# Main_Power.net
KiCad netlist of a schematic drawn in Altium Designer
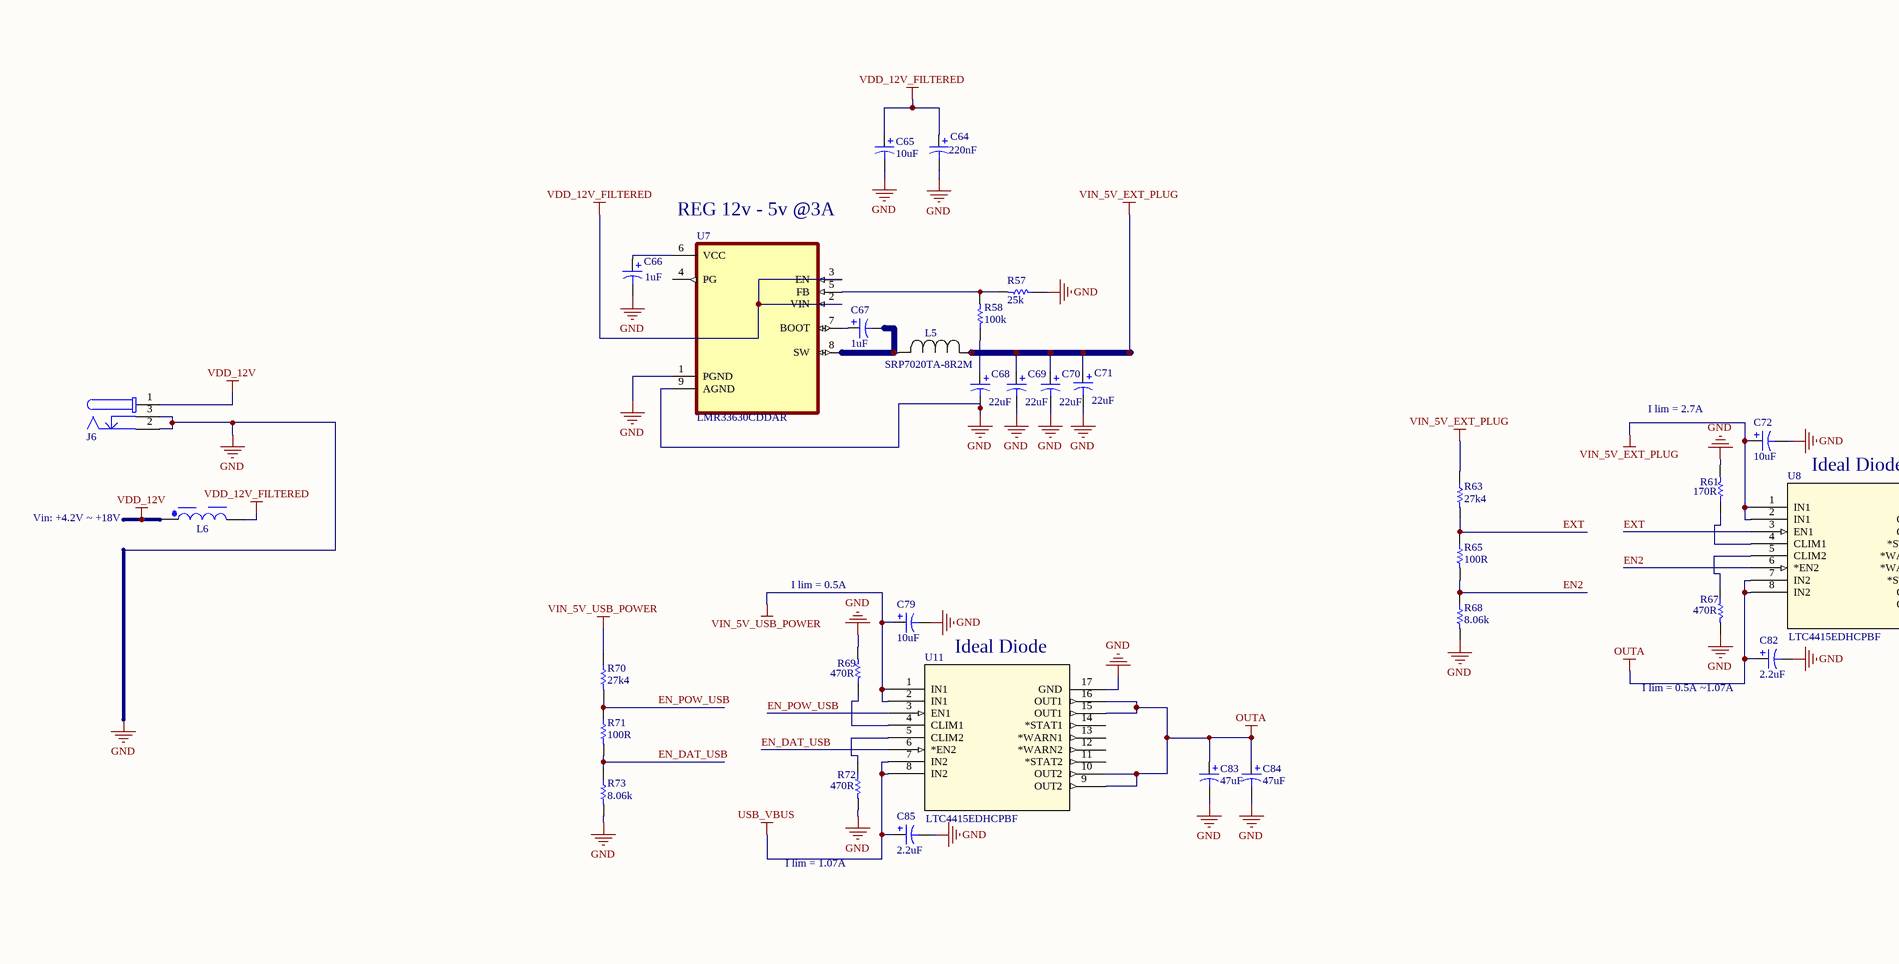
[diagram p0: Main_Power.SchDoc, top left]
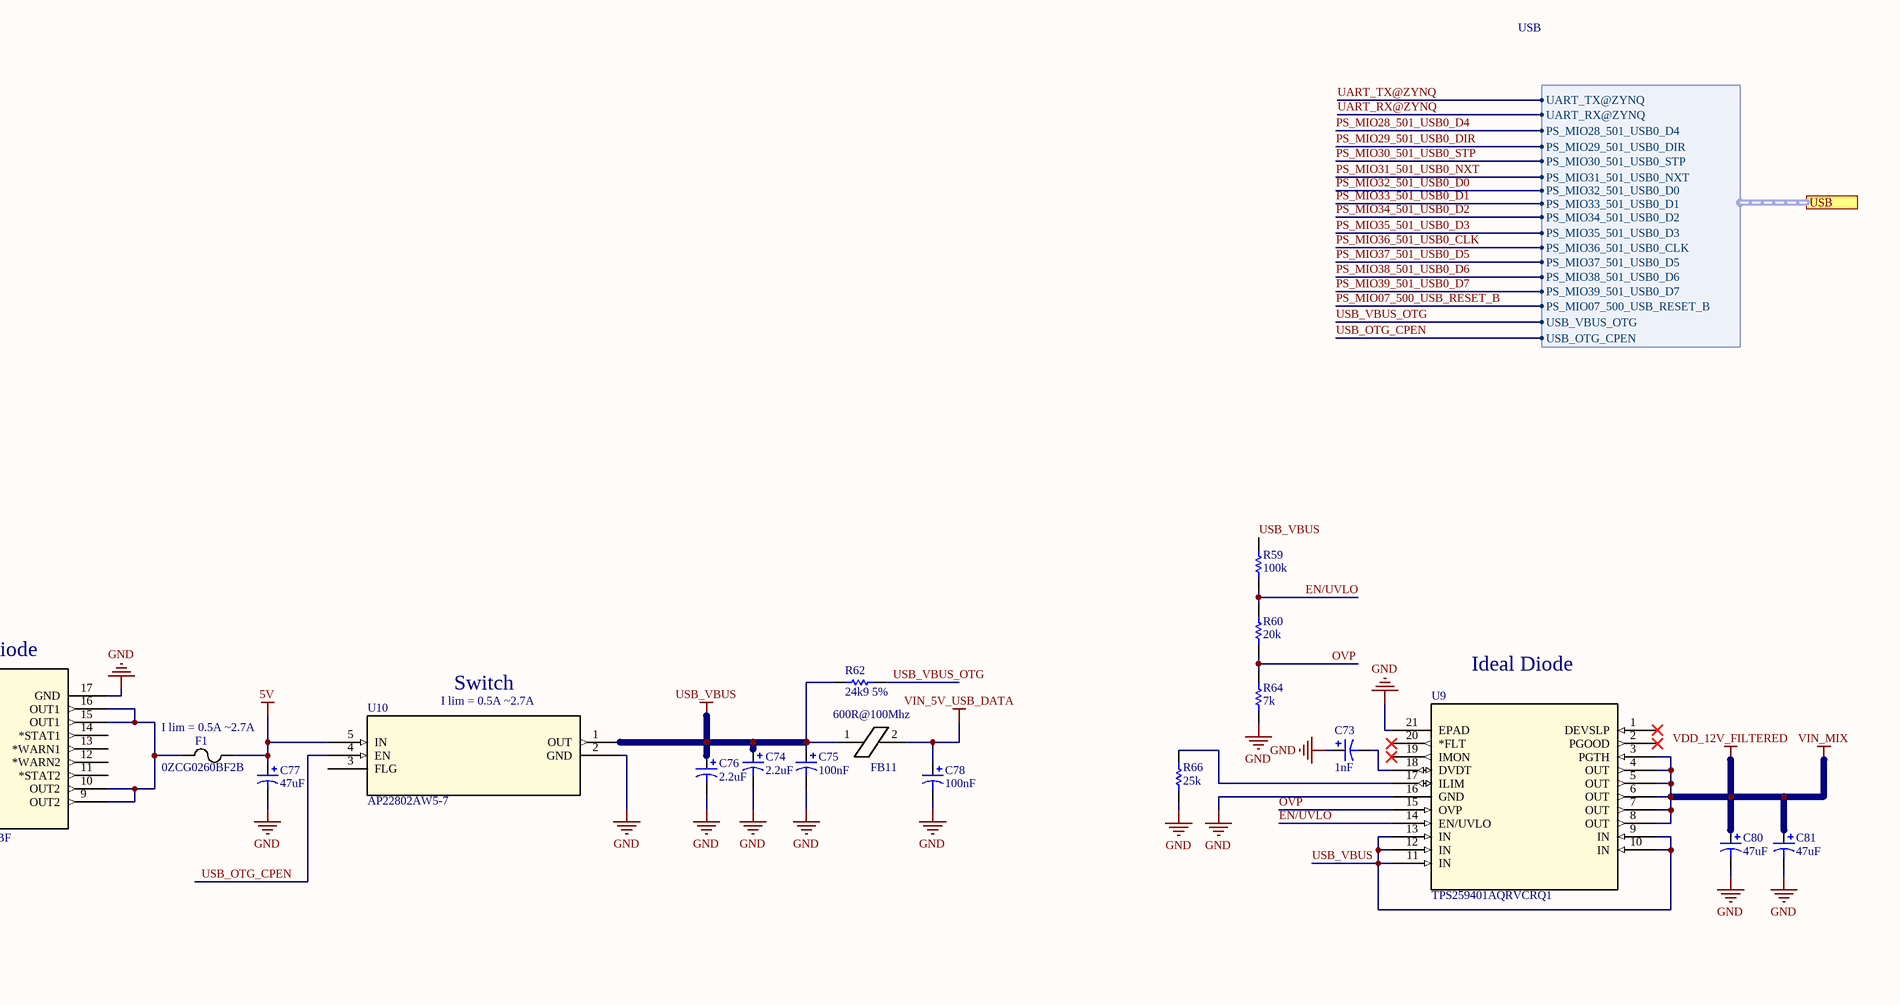
[diagram p1: Main_Power.SchDoc, top right]
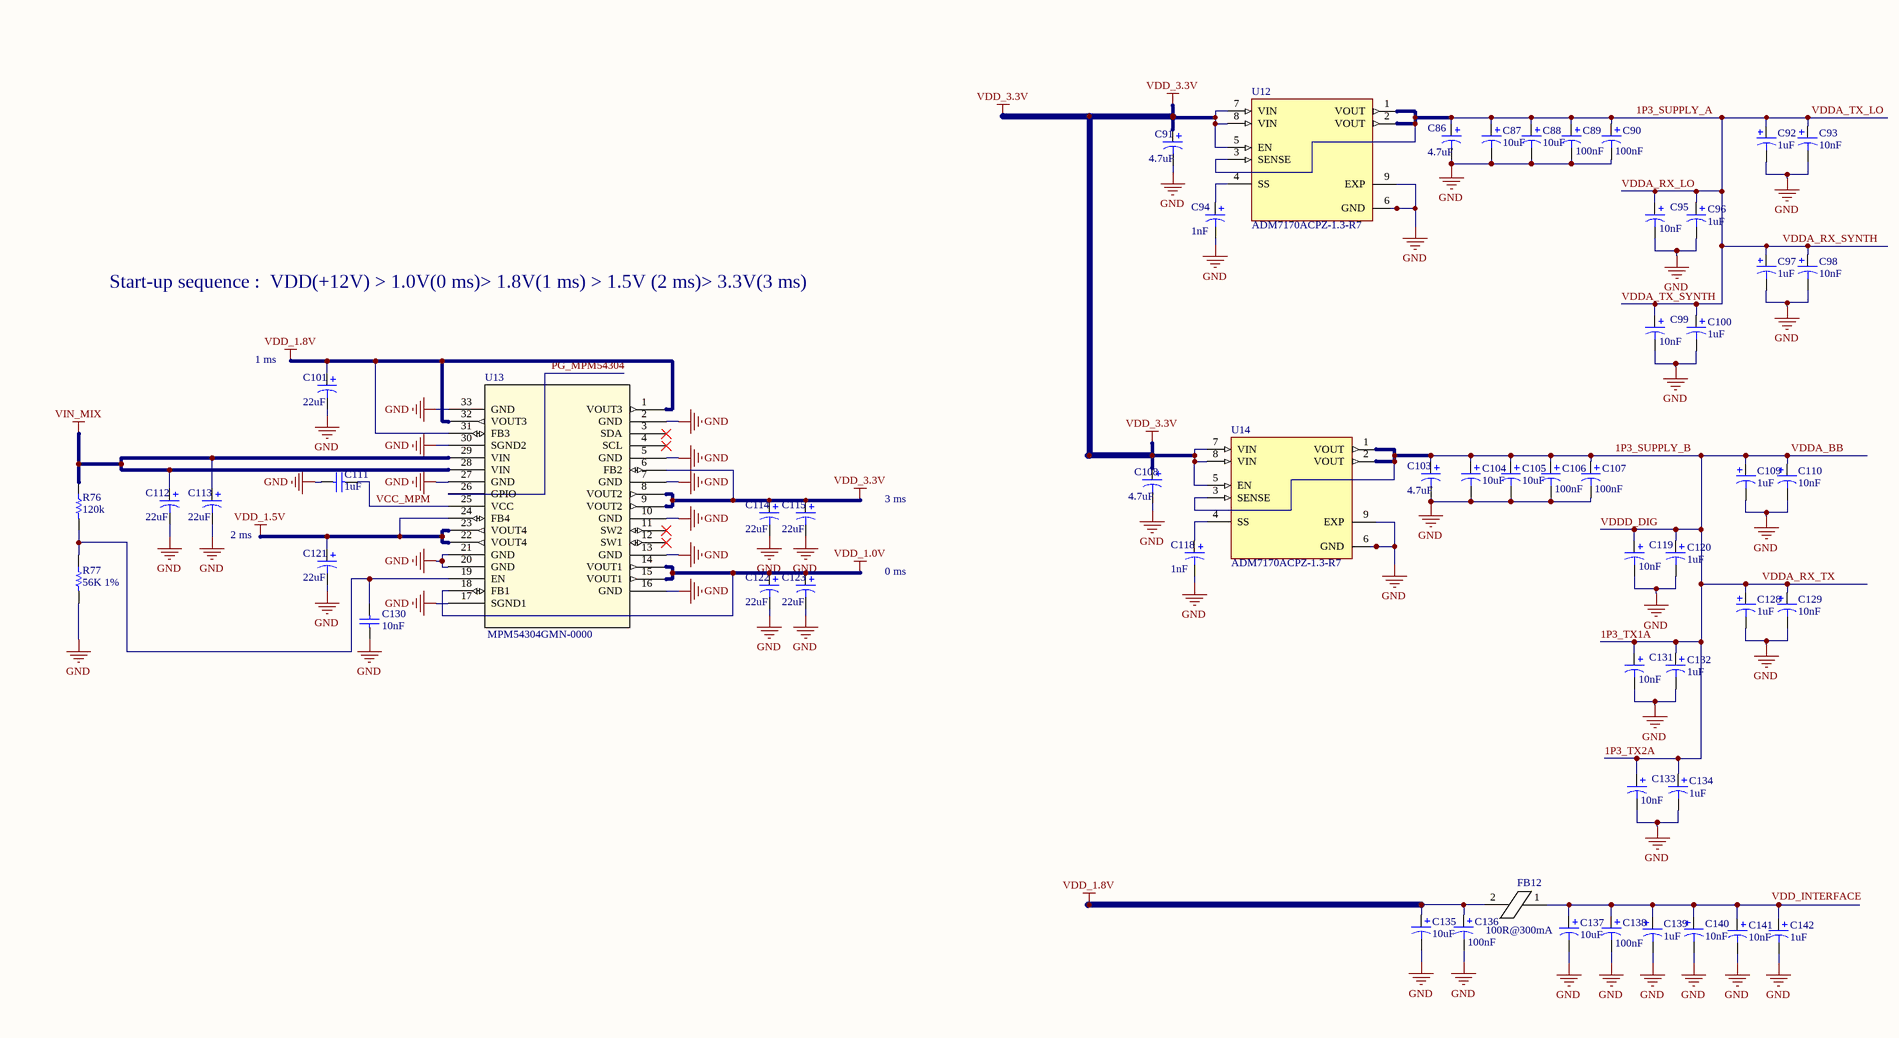
[diagram p2: Main_Power.SchDoc, bottom left]
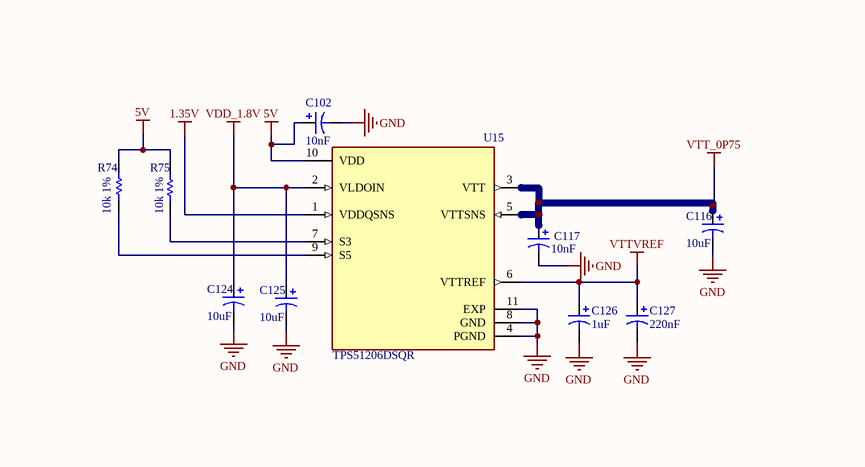
[diagram p3: Main_Power.SchDoc, bottom right]

(export (version "E")
  (design (tool "Eeschema 10.0.6"))
  (components
    (comp (ref "C64")
      (value "220nF")
      (footprint "C0805")
      (description "Polarized Capacitor (Surface Mount)")
      (fields (field (name "Comment") "Pol3") (field (name "PUBLISHER") "Altium Limited"))
      (libsource (lib "Miscellaneous Devices") (part "Cap Pol3"))
    )
    (comp (ref "C65")
      (value "10uF")
      (footprint "C0805")
      (description "Polarized Capacitor (Surface Mount)")
      (fields (field (name "Comment") "Cap Pol3") (field (name "PUBLISHER") "Altium Limited"))
      (libsource (lib "Miscellaneous Devices") (part "Cap Pol3"))
    )
    (comp (ref "C66")
      (value "1uF")
      (footprint "C0805")
      (description "Polarized Capacitor (Surface Mount)")
      (fields (field (name "Comment") "Pol3") (field (name "PUBLISHER") "Altium Limited"))
      (libsource (lib "Miscellaneous Devices") (part "Cap Pol3"))
    )
    (comp (ref "C67")
      (value "1uF")
      (footprint "C0805")
      (description "Polarized Capacitor (Surface Mount)")
      (fields (field (name "Comment") "Pol3") (field (name "PUBLISHER") "Altium Limited"))
      (libsource (lib "Miscellaneous Devices") (part "Cap Pol3"))
    )
    (comp (ref "C68")
      (value "22uF")
      (footprint "C0805")
      (description "Polarized Capacitor (Surface Mount)")
      (fields (field (name "Comment") "Pol3") (field (name "PUBLISHER") "Altium Limited"))
      (libsource (lib "Miscellaneous Devices") (part "Cap Pol3"))
    )
    (comp (ref "C69")
      (value "22uF")
      (footprint "C0805")
      (description "Polarized Capacitor (Surface Mount)")
      (fields (field (name "Comment") "Pol3") (field (name "PUBLISHER") "Altium Limited"))
      (libsource (lib "Miscellaneous Devices") (part "Cap Pol3"))
    )
    (comp (ref "C70")
      (value "22uF")
      (footprint "C0805")
      (description "Polarized Capacitor (Surface Mount)")
      (fields (field (name "Comment") "Pol3") (field (name "PUBLISHER") "Altium Limited"))
      (libsource (lib "Miscellaneous Devices") (part "Cap Pol3"))
    )
    (comp (ref "C71")
      (value "22uF")
      (footprint "C0805")
      (description "Polarized Capacitor (Surface Mount)")
      (fields (field (name "Comment") "Pol3") (field (name "PUBLISHER") "Altium Limited"))
      (libsource (lib "Miscellaneous Devices") (part "Cap Pol3"))
    )
    (comp (ref "C72")
      (value "10uF")
      (footprint "C0805")
      (description "Polarized Capacitor (Surface Mount)")
      (fields (field (name "Comment") "Cap Pol3") (field (name "PUBLISHER") "Altium Limited"))
      (libsource (lib "Miscellaneous Devices") (part "Cap Pol3"))
    )
    (comp (ref "C73")
      (value "1nF")
      (footprint "C0805")
      (description "Polarized Capacitor (Surface Mount)")
      (fields (field (name "Comment") "Cap Pol3") (field (name "PUBLISHER") "Altium Limited"))
      (libsource (lib "Miscellaneous Devices") (part "Cap Pol3"))
    )
    (comp (ref "C74")
      (value "2.2uF")
      (footprint "C0805")
      (description "Polarized Capacitor (Surface Mount)")
      (fields (field (name "Comment") "Cap Pol3") (field (name "PUBLISHER") "Altium Limited"))
      (libsource (lib "Miscellaneous Devices") (part "Cap Pol3"))
    )
    (comp (ref "C75")
      (value "100nF")
      (footprint "C0805")
      (description "Polarized Capacitor (Surface Mount)")
      (fields (field (name "Comment") "Cap Pol3") (field (name "PUBLISHER") "Altium Limited"))
      (libsource (lib "Miscellaneous Devices") (part "Cap Pol3"))
    )
    (comp (ref "C76")
      (value "2.2uF")
      (footprint "C0805")
      (description "Polarized Capacitor (Surface Mount)")
      (fields (field (name "Comment") "Cap Pol3") (field (name "PUBLISHER") "Altium Limited"))
      (libsource (lib "Miscellaneous Devices") (part "Cap Pol3"))
    )
    (comp (ref "C77")
      (value "47uF")
      (footprint "C0805")
      (description "Polarized Capacitor (Surface Mount)")
      (fields (field (name "Comment") "Cap Pol3") (field (name "PUBLISHER") "Altium Limited"))
      (libsource (lib "Miscellaneous Devices") (part "Cap Pol3"))
    )
    (comp (ref "C78")
      (value "100nF")
      (footprint "C0805")
      (description "Polarized Capacitor (Surface Mount)")
      (fields (field (name "Comment") "Cap Pol3") (field (name "PUBLISHER") "Altium Limited"))
      (libsource (lib "Miscellaneous Devices") (part "Cap Pol3"))
    )
    (comp (ref "C79")
      (value "10uF")
      (footprint "C0805")
      (description "Polarized Capacitor (Surface Mount)")
      (fields (field (name "Comment") "Cap Pol3") (field (name "PUBLISHER") "Altium Limited"))
      (libsource (lib "Miscellaneous Devices") (part "Cap Pol3"))
    )
    (comp (ref "C80")
      (value "47uF")
      (footprint "C0805")
      (description "Polarized Capacitor (Surface Mount)")
      (fields (field (name "Comment") "Cap Pol3") (field (name "PUBLISHER") "Altium Limited"))
      (libsource (lib "Miscellaneous Devices") (part "Cap Pol3"))
    )
    (comp (ref "C81")
      (value "47uF")
      (footprint "C0805")
      (description "Polarized Capacitor (Surface Mount)")
      (fields (field (name "Comment") "Cap Pol3") (field (name "PUBLISHER") "Altium Limited"))
      (libsource (lib "Miscellaneous Devices") (part "Cap Pol3"))
    )
    (comp (ref "C82")
      (value "2.2uF")
      (footprint "C0805")
      (description "Polarized Capacitor (Surface Mount)")
      (fields (field (name "Comment") "Cap Pol3") (field (name "PUBLISHER") "Altium Limited"))
      (libsource (lib "Miscellaneous Devices") (part "Cap Pol3"))
    )
    (comp (ref "C83")
      (value "47uF")
      (footprint "C0805")
      (description "Polarized Capacitor (Surface Mount)")
      (fields (field (name "Comment") "Cap Pol3") (field (name "PUBLISHER") "Altium Limited"))
      (libsource (lib "Miscellaneous Devices") (part "Cap Pol3"))
    )
    (comp (ref "C84")
      (value "47uF")
      (footprint "C0805")
      (description "Polarized Capacitor (Surface Mount)")
      (fields (field (name "Comment") "Cap Pol3") (field (name "PUBLISHER") "Altium Limited"))
      (libsource (lib "Miscellaneous Devices") (part "Cap Pol3"))
    )
    (comp (ref "C85")
      (value "2.2uF")
      (footprint "C0805")
      (description "Polarized Capacitor (Surface Mount)")
      (fields (field (name "Comment") "Cap Pol3") (field (name "PUBLISHER") "Altium Limited"))
      (libsource (lib "Miscellaneous Devices") (part "Cap Pol3"))
    )
    (comp (ref "C86")
      (value "4.7uF")
      (footprint "C0805")
      (description "Polarized Capacitor (Surface Mount)")
      (fields (field (name "Comment") "Pol3") (field (name "PUBLISHER") "Altium Limited"))
      (libsource (lib "Miscellaneous Devices") (part "Cap Pol3"))
    )
    (comp (ref "C87")
      (value "10uF")
      (footprint "C0805")
      (description "Polarized Capacitor (Surface Mount)")
      (fields (field (name "Comment") "Cap Pol3") (field (name "PUBLISHER") "Altium Limited"))
      (libsource (lib "Miscellaneous Devices") (part "Cap Pol3"))
    )
    (comp (ref "C88")
      (value "10uF")
      (footprint "C0805")
      (description "Polarized Capacitor (Surface Mount)")
      (fields (field (name "Comment") "Cap Pol3") (field (name "PUBLISHER") "Altium Limited"))
      (libsource (lib "Miscellaneous Devices") (part "Cap Pol3"))
    )
    (comp (ref "C89")
      (value "100nF")
      (footprint "C0805")
      (description "Polarized Capacitor (Surface Mount)")
      (fields (field (name "Comment") "Cap Pol3") (field (name "PUBLISHER") "Altium Limited"))
      (libsource (lib "Miscellaneous Devices") (part "Cap Pol3"))
    )
    (comp (ref "C90")
      (value "100nF")
      (footprint "C0805")
      (description "Polarized Capacitor (Surface Mount)")
      (fields (field (name "Comment") "Cap Pol3") (field (name "PUBLISHER") "Altium Limited"))
      (libsource (lib "Miscellaneous Devices") (part "Cap Pol3"))
    )
    (comp (ref "C91")
      (value "4.7uF")
      (footprint "C0805")
      (description "Polarized Capacitor (Surface Mount)")
      (fields (field (name "Comment") "Pol3") (field (name "PUBLISHER") "Altium Limited"))
      (libsource (lib "Miscellaneous Devices") (part "Cap Pol3"))
    )
    (comp (ref "C92")
      (value "1uF")
      (footprint "C0805")
      (description "Polarized Capacitor (Surface Mount)")
      (fields (field (name "Comment") "Cap Pol3") (field (name "PUBLISHER") "Altium Limited"))
      (libsource (lib "") (part "Cap Pol3_1"))
    )
    (comp (ref "C93")
      (value "10nF")
      (footprint "C0805")
      (description "Polarized Capacitor (Surface Mount)")
      (fields (field (name "Comment") "Cap Pol3") (field (name "PUBLISHER") "Altium Limited"))
      (libsource (lib "") (part "Cap Pol3_1"))
    )
    (comp (ref "C94")
      (value "1nF")
      (footprint "C0805")
      (description "Polarized Capacitor (Surface Mount)")
      (fields (field (name "Comment") "Pol3") (field (name "PUBLISHER") "Altium Limited"))
      (libsource (lib "Miscellaneous Devices") (part "Cap Pol3"))
    )
    (comp (ref "C95")
      (value "10nF")
      (footprint "C0805")
      (description "Polarized Capacitor (Surface Mount)")
      (fields (field (name "Comment") "Cap Pol3") (field (name "PUBLISHER") "Altium Limited"))
      (libsource (lib "Miscellaneous Devices") (part "Cap Pol3"))
    )
    (comp (ref "C96")
      (value "1uF")
      (footprint "C0805")
      (description "Polarized Capacitor (Surface Mount)")
      (fields (field (name "Comment") "Cap Pol3") (field (name "PUBLISHER") "Altium Limited"))
      (libsource (lib "Miscellaneous Devices") (part "Cap Pol3"))
    )
    (comp (ref "C97")
      (value "1uF")
      (footprint "C0805")
      (description "Polarized Capacitor (Surface Mount)")
      (fields (field (name "Comment") "Cap Pol3") (field (name "PUBLISHER") "Altium Limited"))
      (libsource (lib "") (part "Cap Pol3_1"))
    )
    (comp (ref "C98")
      (value "10nF")
      (footprint "C0805")
      (description "Polarized Capacitor (Surface Mount)")
      (fields (field (name "Comment") "Cap Pol3") (field (name "PUBLISHER") "Altium Limited"))
      (libsource (lib "") (part "Cap Pol3_1"))
    )
    (comp (ref "C99")
      (value "10nF")
      (footprint "C0805")
      (description "Polarized Capacitor (Surface Mount)")
      (fields (field (name "Comment") "Cap Pol3") (field (name "PUBLISHER") "Altium Limited"))
      (libsource (lib "Miscellaneous Devices") (part "Cap Pol3"))
    )
    (comp (ref "C100")
      (value "1uF")
      (footprint "C0805")
      (description "Polarized Capacitor (Surface Mount)")
      (fields (field (name "Comment") "Cap Pol3") (field (name "PUBLISHER") "Altium Limited"))
      (libsource (lib "Miscellaneous Devices") (part "Cap Pol3"))
    )
    (comp (ref "C101")
      (value "22uF")
      (footprint "C0805")
      (description "Polarized Capacitor (Surface Mount)")
      (fields (field (name "Comment") "Pol3") (field (name "PUBLISHER") "Altium Limited"))
      (libsource (lib "Miscellaneous Devices") (part "Cap Pol3"))
    )
    (comp (ref "C102")
      (value "10nF")
      (footprint "C0805")
      (description "Polarized Capacitor (Surface Mount)")
      (fields (field (name "Comment") "Cap Pol3") (field (name "PUBLISHER") "Altium Limited"))
      (libsource (lib "Miscellaneous Devices") (part "Cap Pol3"))
    )
    (comp (ref "C103")
      (value "4.7uF")
      (footprint "C0805")
      (description "Polarized Capacitor (Surface Mount)")
      (fields (field (name "Comment") "Pol3") (field (name "PUBLISHER") "Altium Limited"))
      (libsource (lib "Miscellaneous Devices") (part "Cap Pol3"))
    )
    (comp (ref "C104")
      (value "10uF")
      (footprint "C0805")
      (description "Polarized Capacitor (Surface Mount)")
      (fields (field (name "Comment") "Cap Pol3") (field (name "PUBLISHER") "Altium Limited"))
      (libsource (lib "Miscellaneous Devices") (part "Cap Pol3"))
    )
    (comp (ref "C105")
      (value "10uF")
      (footprint "C0805")
      (description "Polarized Capacitor (Surface Mount)")
      (fields (field (name "Comment") "Cap Pol3") (field (name "PUBLISHER") "Altium Limited"))
      (libsource (lib "Miscellaneous Devices") (part "Cap Pol3"))
    )
    (comp (ref "C106")
      (value "100nF")
      (footprint "C0805")
      (description "Polarized Capacitor (Surface Mount)")
      (fields (field (name "Comment") "Cap Pol3") (field (name "PUBLISHER") "Altium Limited"))
      (libsource (lib "Miscellaneous Devices") (part "Cap Pol3"))
    )
    (comp (ref "C107")
      (value "100nF")
      (footprint "C0805")
      (description "Polarized Capacitor (Surface Mount)")
      (fields (field (name "Comment") "Cap Pol3") (field (name "PUBLISHER") "Altium Limited"))
      (libsource (lib "Miscellaneous Devices") (part "Cap Pol3"))
    )
    (comp (ref "C108")
      (value "4.7uF")
      (footprint "C0805")
      (description "Polarized Capacitor (Surface Mount)")
      (fields (field (name "Comment") "Pol3") (field (name "PUBLISHER") "Altium Limited"))
      (libsource (lib "Miscellaneous Devices") (part "Cap Pol3"))
    )
    (comp (ref "C109")
      (value "1uF")
      (footprint "C0805")
      (description "Polarized Capacitor (Surface Mount)")
      (fields (field (name "Comment") "Cap Pol3") (field (name "PUBLISHER") "Altium Limited"))
      (libsource (lib "") (part "Cap Pol3_1"))
    )
    (comp (ref "C110")
      (value "10nF")
      (footprint "C0805")
      (description "Polarized Capacitor (Surface Mount)")
      (fields (field (name "Comment") "Cap Pol3") (field (name "PUBLISHER") "Altium Limited"))
      (libsource (lib "") (part "Cap Pol3_1"))
    )
    (comp (ref "C111")
      (value "1uF")
      (footprint "1608[0603]")
      (description "Capacitor (Semiconductor SIM Model)")
      (fields (field (name "PUBLISHER") "Altium Limited"))
      (libsource (lib "Miscellaneous Devices") (part "Cap Semi"))
    )
    (comp (ref "C112")
      (value "22uF")
      (footprint "C0805")
      (description "Polarized Capacitor (Surface Mount)")
      (fields (field (name "Comment") "Pol3") (field (name "PUBLISHER") "Altium Limited"))
      (libsource (lib "Miscellaneous Devices") (part "Cap Pol3"))
    )
    (comp (ref "C113")
      (value "22uF")
      (footprint "C0805")
      (description "Polarized Capacitor (Surface Mount)")
      (fields (field (name "Comment") "Pol3") (field (name "PUBLISHER") "Altium Limited"))
      (libsource (lib "Miscellaneous Devices") (part "Cap Pol3"))
    )
    (comp (ref "C114")
      (value "22uF")
      (footprint "C0805")
      (description "Polarized Capacitor (Surface Mount)")
      (fields (field (name "Comment") "Pol3") (field (name "PUBLISHER") "Altium Limited"))
      (libsource (lib "Miscellaneous Devices") (part "Cap Pol3"))
    )
    (comp (ref "C115")
      (value "22uF")
      (footprint "C0805")
      (description "Polarized Capacitor (Surface Mount)")
      (fields (field (name "Comment") "Pol3") (field (name "PUBLISHER") "Altium Limited"))
      (libsource (lib "Miscellaneous Devices") (part "Cap Pol3"))
    )
    (comp (ref "C116")
      (value "10uF")
      (footprint "C0805")
      (description "Polarized Capacitor (Surface Mount)")
      (fields (field (name "Comment") "Pol3") (field (name "PUBLISHER") "Altium Limited"))
      (libsource (lib "Miscellaneous Devices") (part "Cap Pol3"))
    )
    (comp (ref "C117")
      (value "10nF")
      (footprint "C0805")
      (description "Polarized Capacitor (Surface Mount)")
      (fields (field (name "Comment") "Cap Pol3") (field (name "PUBLISHER") "Altium Limited"))
      (libsource (lib "Miscellaneous Devices") (part "Cap Pol3"))
    )
    (comp (ref "C118")
      (value "1nF")
      (footprint "C0805")
      (description "Polarized Capacitor (Surface Mount)")
      (fields (field (name "Comment") "Pol3") (field (name "PUBLISHER") "Altium Limited"))
      (libsource (lib "Miscellaneous Devices") (part "Cap Pol3"))
    )
    (comp (ref "C119")
      (value "10nF")
      (footprint "C0805")
      (description "Polarized Capacitor (Surface Mount)")
      (fields (field (name "Comment") "Cap Pol3") (field (name "PUBLISHER") "Altium Limited"))
      (libsource (lib "Miscellaneous Devices") (part "Cap Pol3"))
    )
    (comp (ref "C120")
      (value "1uF")
      (footprint "C0805")
      (description "Polarized Capacitor (Surface Mount)")
      (fields (field (name "Comment") "Cap Pol3") (field (name "PUBLISHER") "Altium Limited"))
      (libsource (lib "Miscellaneous Devices") (part "Cap Pol3"))
    )
    (comp (ref "C121")
      (value "22uF")
      (footprint "C0805")
      (description "Polarized Capacitor (Surface Mount)")
      (fields (field (name "Comment") "Pol3") (field (name "PUBLISHER") "Altium Limited"))
      (libsource (lib "Miscellaneous Devices") (part "Cap Pol3"))
    )
    (comp (ref "C122")
      (value "22uF")
      (footprint "C0805")
      (description "Polarized Capacitor (Surface Mount)")
      (fields (field (name "Comment") "Pol3") (field (name "PUBLISHER") "Altium Limited"))
      (libsource (lib "Miscellaneous Devices") (part "Cap Pol3"))
    )
    (comp (ref "C123")
      (value "22uF")
      (footprint "C0805")
      (description "Polarized Capacitor (Surface Mount)")
      (fields (field (name "Comment") "Pol3") (field (name "PUBLISHER") "Altium Limited"))
      (libsource (lib "Miscellaneous Devices") (part "Cap Pol3"))
    )
    (comp (ref "C124")
      (value "10uF")
      (footprint "C0805")
      (description "Polarized Capacitor (Surface Mount)")
      (fields (field (name "Comment") "Pol3") (field (name "PUBLISHER") "Altium Limited"))
      (libsource (lib "Miscellaneous Devices") (part "Cap Pol3"))
    )
    (comp (ref "C125")
      (value "10uF")
      (footprint "C0805")
      (description "Polarized Capacitor (Surface Mount)")
      (fields (field (name "Comment") "Pol3") (field (name "PUBLISHER") "Altium Limited"))
      (libsource (lib "Miscellaneous Devices") (part "Cap Pol3"))
    )
    (comp (ref "C126")
      (value "1uF")
      (footprint "C0805")
      (description "Polarized Capacitor (Surface Mount)")
      (fields (field (name "Comment") "Cap Pol3") (field (name "PUBLISHER") "Altium Limited"))
      (libsource (lib "Miscellaneous Devices") (part "Cap Pol3"))
    )
    (comp (ref "C127")
      (value "220nF")
      (footprint "C0805")
      (description "Polarized Capacitor (Surface Mount)")
      (fields (field (name "Comment") "Cap Pol3") (field (name "PUBLISHER") "Altium Limited"))
      (libsource (lib "Miscellaneous Devices") (part "Cap Pol3"))
    )
    (comp (ref "C128")
      (value "1uF")
      (footprint "C0805")
      (description "Polarized Capacitor (Surface Mount)")
      (fields (field (name "Comment") "Cap Pol3") (field (name "PUBLISHER") "Altium Limited"))
      (libsource (lib "") (part "Cap Pol3_1"))
    )
    (comp (ref "C129")
      (value "10nF")
      (footprint "C0805")
      (description "Polarized Capacitor (Surface Mount)")
      (fields (field (name "Comment") "Cap Pol3") (field (name "PUBLISHER") "Altium Limited"))
      (libsource (lib "") (part "Cap Pol3_1"))
    )
    (comp (ref "C130")
      (value "10nF")
      (footprint "1608[0603]")
      (description "Capacitor (Semiconductor SIM Model)")
      (fields (field (name "PUBLISHER") "Altium Limited"))
      (libsource (lib "Miscellaneous Devices") (part "Cap Semi"))
    )
    (comp (ref "C131")
      (value "10nF")
      (footprint "C0805")
      (description "Polarized Capacitor (Surface Mount)")
      (fields (field (name "Comment") "Cap Pol3") (field (name "PUBLISHER") "Altium Limited"))
      (libsource (lib "Miscellaneous Devices") (part "Cap Pol3"))
    )
    (comp (ref "C132")
      (value "1uF")
      (footprint "C0805")
      (description "Polarized Capacitor (Surface Mount)")
      (fields (field (name "Comment") "Cap Pol3") (field (name "PUBLISHER") "Altium Limited"))
      (libsource (lib "Miscellaneous Devices") (part "Cap Pol3"))
    )
    (comp (ref "C133")
      (value "10nF")
      (footprint "C0805")
      (description "Polarized Capacitor (Surface Mount)")
      (fields (field (name "Comment") "Cap Pol3") (field (name "PUBLISHER") "Altium Limited"))
      (libsource (lib "Miscellaneous Devices") (part "Cap Pol3"))
    )
    (comp (ref "C134")
      (value "1uF")
      (footprint "C0805")
      (description "Polarized Capacitor (Surface Mount)")
      (fields (field (name "Comment") "Cap Pol3") (field (name "PUBLISHER") "Altium Limited"))
      (libsource (lib "Miscellaneous Devices") (part "Cap Pol3"))
    )
    (comp (ref "C135")
      (value "10uF")
      (footprint "C0805")
      (description "Polarized Capacitor (Surface Mount)")
      (fields (field (name "Comment") "Cap Pol3") (field (name "PUBLISHER") "Altium Limited"))
      (libsource (lib "Miscellaneous Devices") (part "Cap Pol3"))
    )
    (comp (ref "C136")
      (value "100nF")
      (footprint "C0805")
      (description "Polarized Capacitor (Surface Mount)")
      (fields (field (name "Comment") "Cap Pol3") (field (name "PUBLISHER") "Altium Limited"))
      (libsource (lib "Miscellaneous Devices") (part "Cap Pol3"))
    )
    (comp (ref "C137")
      (value "10uF")
      (footprint "C0805")
      (description "Polarized Capacitor (Surface Mount)")
      (fields (field (name "Comment") "Cap Pol3") (field (name "PUBLISHER") "Altium Limited"))
      (libsource (lib "Miscellaneous Devices") (part "Cap Pol3"))
    )
    (comp (ref "C138")
      (value "100nF")
      (footprint "C0805")
      (description "Polarized Capacitor (Surface Mount)")
      (fields (field (name "Comment") "Cap Pol3") (field (name "PUBLISHER") "Altium Limited"))
      (libsource (lib "Miscellaneous Devices") (part "Cap Pol3"))
    )
    (comp (ref "C139")
      (value "1uF")
      (footprint "C0805")
      (description "Polarized Capacitor (Surface Mount)")
      (fields (field (name "Comment") "Cap Pol3") (field (name "PUBLISHER") "Altium Limited"))
      (libsource (lib "") (part "Cap Pol3_1"))
    )
    (comp (ref "C140")
      (value "10nF")
      (footprint "C0805")
      (description "Polarized Capacitor (Surface Mount)")
      (fields (field (name "Comment") "Cap Pol3") (field (name "PUBLISHER") "Altium Limited"))
      (libsource (lib "") (part "Cap Pol3_1"))
    )
    (comp (ref "C141")
      (value "10nF")
      (footprint "C0805")
      (description "Polarized Capacitor (Surface Mount)")
      (fields (field (name "Comment") "Cap Pol3") (field (name "PUBLISHER") "Altium Limited"))
      (libsource (lib "Miscellaneous Devices") (part "Cap Pol3"))
    )
    (comp (ref "C142")
      (value "1uF")
      (footprint "C0805")
      (description "Polarized Capacitor (Surface Mount)")
      (fields (field (name "Comment") "Cap Pol3") (field (name "PUBLISHER") "Altium Limited"))
      (libsource (lib "Miscellaneous Devices") (part "Cap Pol3"))
    )
    (comp (ref "F1")
      (value "0ZCG0260BF2B")
      (footprint "0ZCG_BEL")
      (description "No Description Available")
      (libsource (lib "0ZCG0260BF2B") (part "0ZCG0260BF2B"))
    )
    (comp (ref "FB11")
      (value "FERRITA")
      (footprint "0805R")
      (libsource (lib "lib_protel_HC") (part "FERRITA"))
    )
    (comp (ref "FB12")
      (value "FERRITA")
      (footprint "0805R")
      (libsource (lib "lib_protel_HC") (part "FERRITA"))
    )
    (comp (ref "J6")
      (value "694108301002")
      (footprint "694108301002")
      (description "WR-DC DC Power Jack Connector, Male, Right Angled, 24V, 5A")
      (fields (field (name "MANUFACTURER") "Wurth Elektronik"))
      (libsource (lib "Altium_WR-DC (rev22a)") (part "694108301002"))
    )
    (comp (ref "L5")
      (value "SRP7020TA-8R2M")
      (footprint "IND_SRP7020TA-8R2M_BRN")
      (description "No Description Available")
      (libsource (lib "SRP7020TA-8R2M") (part "SRP7020TA-8R2M"))
    )
    (comp (ref "L6")
      (value "4.7uH, 2.9A")
      (footprint "WE-PD_7332R")
      (description "WE-PD SMT Power Inductor, size 7332R, 4.7uH, 2.9A, 39mOhm")
      (fields
        (field (name "MANUFACTURER PART NUMBER") "7447789004")
        (field (name "MANUFACTURER") "Wurth Elektronik")
      )
      (libsource (lib "Altium_WE-PD_rev22g") (part "7447789004"))
    )
    (comp (ref "R57")
      (value "25k")
      (footprint "0603")
      (description "Resistor")
      (fields
        (field (name "MANUFACTURER") "Generic Components")
        (field (name "Comment") "Res1")
        (field (name "PUBLISHER") "Altium Limited")
      )
      (libsource (lib "lib_protel_HC") (part "Res1_1"))
    )
    (comp (ref "R58")
      (value "100k")
      (footprint "0603")
      (description "Resistor")
      (fields
        (field (name "MANUFACTURER") "Generic Components")
        (field (name "Comment") "Res1")
        (field (name "PUBLISHER") "Altium Limited")
      )
      (libsource (lib "lib_protel_HC") (part "Res1_1"))
    )
    (comp (ref "R59")
      (value "100k")
      (footprint "0603")
      (description "Resistor")
      (fields
        (field (name "MANUFACTURER") "Generic Components")
        (field (name "Comment") "Res1")
        (field (name "PUBLISHER") "Altium Limited")
      )
      (libsource (lib "lib_protel_HC") (part "Res1_1"))
    )
    (comp (ref "R60")
      (value "20k")
      (footprint "0603")
      (description "Resistor")
      (fields
        (field (name "MANUFACTURER") "Generic Components")
        (field (name "Comment") "Res1")
        (field (name "PUBLISHER") "Altium Limited")
      )
      (libsource (lib "lib_protel_HC") (part "Res1_1"))
    )
    (comp (ref "R61")
      (value "170R")
      (footprint "0603")
      (description "Resistor")
      (fields
        (field (name "MANUFACTURER") "Generic Components")
        (field (name "Comment") "Res1")
        (field (name "PUBLISHER") "Altium Limited")
      )
      (libsource (lib "lib_protel_HC") (part "Res1_1"))
    )
    (comp (ref "R62")
      (value "24k9 5%")
      (footprint "0603")
      (description "Resistor")
      (fields
        (field (name "MANUFACTURER") "Generic Components")
        (field (name "Comment") "Res1")
        (field (name "PUBLISHER") "Altium Limited")
      )
      (libsource (lib "lib_protel_HC") (part "Res1_1"))
    )
    (comp (ref "R63")
      (value "27k4")
      (footprint "0603")
      (description "Resistor")
      (fields
        (field (name "MANUFACTURER") "Generic Components")
        (field (name "Comment") "Res1")
        (field (name "PUBLISHER") "Altium Limited")
      )
      (libsource (lib "lib_protel_HC") (part "Res1_1"))
    )
    (comp (ref "R64")
      (value "7k")
      (footprint "0603")
      (description "Resistor")
      (fields
        (field (name "MANUFACTURER") "Generic Components")
        (field (name "Comment") "Res1")
        (field (name "PUBLISHER") "Altium Limited")
      )
      (libsource (lib "lib_protel_HC") (part "Res1_1"))
    )
    (comp (ref "R65")
      (value "100R")
      (footprint "0603")
      (description "Resistor")
      (fields
        (field (name "MANUFACTURER") "Generic Components")
        (field (name "Comment") "Res1")
        (field (name "PUBLISHER") "Altium Limited")
      )
      (libsource (lib "lib_protel_HC") (part "Res1_1"))
    )
    (comp (ref "R66")
      (value "25k")
      (footprint "0603")
      (description "Resistor")
      (fields
        (field (name "MANUFACTURER") "Generic Components")
        (field (name "Comment") "Res1")
        (field (name "PUBLISHER") "Altium Limited")
      )
      (libsource (lib "lib_protel_HC") (part "Res1_1"))
    )
    (comp (ref "R67")
      (value "470R")
      (footprint "0603")
      (description "Resistor")
      (fields
        (field (name "MANUFACTURER") "Generic Components")
        (field (name "Comment") "Res1")
        (field (name "PUBLISHER") "Altium Limited")
      )
      (libsource (lib "lib_protel_HC") (part "Res1_1"))
    )
    (comp (ref "R68")
      (value "8.06k")
      (footprint "0603")
      (description "Resistor")
      (fields
        (field (name "MANUFACTURER") "Generic Components")
        (field (name "Comment") "Res1")
        (field (name "PUBLISHER") "Altium Limited")
      )
      (libsource (lib "lib_protel_HC") (part "Res1_1"))
    )
    (comp (ref "R69")
      (value "470R")
      (footprint "0603")
      (description "Resistor")
      (fields
        (field (name "MANUFACTURER") "Generic Components")
        (field (name "Comment") "Res1")
        (field (name "PUBLISHER") "Altium Limited")
      )
      (libsource (lib "lib_protel_HC") (part "Res1_1"))
    )
    (comp (ref "R70")
      (value "27k4")
      (footprint "0603")
      (description "Resistor")
      (fields
        (field (name "MANUFACTURER") "Generic Components")
        (field (name "Comment") "Res1")
        (field (name "PUBLISHER") "Altium Limited")
      )
      (libsource (lib "lib_protel_HC") (part "Res1_1"))
    )
    (comp (ref "R71")
      (value "100R")
      (footprint "0603")
      (description "Resistor")
      (fields
        (field (name "MANUFACTURER") "Generic Components")
        (field (name "Comment") "Res1")
        (field (name "PUBLISHER") "Altium Limited")
      )
      (libsource (lib "lib_protel_HC") (part "Res1_1"))
    )
    (comp (ref "R72")
      (value "470R")
      (footprint "0603")
      (description "Resistor")
      (fields
        (field (name "MANUFACTURER") "Generic Components")
        (field (name "Comment") "Res1")
        (field (name "PUBLISHER") "Altium Limited")
      )
      (libsource (lib "lib_protel_HC") (part "Res1_1"))
    )
    (comp (ref "R73")
      (value "8.06k")
      (footprint "0603")
      (description "Resistor")
      (fields
        (field (name "MANUFACTURER") "Generic Components")
        (field (name "Comment") "Res1")
        (field (name "PUBLISHER") "Altium Limited")
      )
      (libsource (lib "lib_protel_HC") (part "Res1_1"))
    )
    (comp (ref "R74")
      (value "10k 1%")
      (footprint "0603")
      (description "Resistor")
      (fields
        (field (name "MANUFACTURER") "Generic Components")
        (field (name "Comment") "Res1")
        (field (name "PUBLISHER") "Altium Limited")
      )
      (libsource (lib "lib_protel_HC") (part "Res1_1"))
    )
    (comp (ref "R75")
      (value "10k 1%")
      (footprint "0603")
      (description "Resistor")
      (fields
        (field (name "MANUFACTURER") "Generic Components")
        (field (name "Comment") "Res1")
        (field (name "PUBLISHER") "Altium Limited")
      )
      (libsource (lib "lib_protel_HC") (part "Res1_1"))
    )
    (comp (ref "R76")
      (value "120k")
      (footprint "0603")
      (description "Resistor")
      (fields
        (field (name "MANUFACTURER") "Generic Components")
        (field (name "Comment") "Res1")
        (field (name "PUBLISHER") "Altium Limited")
      )
      (libsource (lib "lib_protel_HC") (part "Res1_1"))
    )
    (comp (ref "R77")
      (value "56K 1%")
      (footprint "0603")
      (description "Resistor")
      (fields
        (field (name "MANUFACTURER") "Generic Components")
        (field (name "Comment") "Res1")
        (field (name "PUBLISHER") "Altium Limited")
      )
      (libsource (lib "lib_protel_HC") (part "Res1_1"))
    )
    (comp (ref "U7")
      (value "LMR33630CDDAR")
      (footprint "VREG_LM5017MR/NOPB")
      (fields (field (name "MF") "Texas Instruments"))
      (libsource (lib "LMR33630CDDAR") (part "LMR33630CDDAR"))
    )
    (comp (ref "U8")
      (value "LTC4415EDHCPBF")
      (footprint "05-08-1872_ADI")
      (description "No Description Available")
      (libsource (lib "LTC4415EDHCPBF") (part "LTC4415EDHCPBF"))
    )
    (comp (ref "U9")
      (value "TPS259401AQRVCRQ1")
      (footprint "WQFN_3QRVCRQ1_TEX")
      (description "No Description Available")
      (libsource (lib "TPS259401AQRVCRQ1") (part "TPS259401AQRVCRQ1"))
    )
    (comp (ref "U10")
      (value "AP22802AW5-7")
      (footprint "SOT25_DIO")
      (description "No Description Available")
      (libsource (lib "AP22802AW5-7") (part "AP22802AW5-7"))
    )
    (comp (ref "U11")
      (value "LTC4415EDHCPBF")
      (footprint "05-08-1872_ADI")
      (description "No Description Available")
      (libsource (lib "LTC4415EDHCPBF") (part "LTC4415EDHCPBF"))
    )
    (comp (ref "U12")
      (value "ADM7170ACPZ-1.3-R7")
      (footprint "SON50P300X300X80-9N")
      (description "6.5 V, 500 mA, Ultralow Noise, High PSRR, Fast Transient Response CMOS LDO")
      (fields (field (name "MF") "Analog Devices"))
      (libsource (lib "ADM7170ACPZ-1.3-R7") (part "ADM7170ACPZ-1.3-R7"))
    )
    (comp (ref "U13")
      (value "MPM54304GMN-0000")
      (footprint "LGA7x7x2_MNP")
      (description "No Description Available")
      (libsource (lib "MPM54304GMN-0000") (part "MPM54304GMN-0000"))
    )
    (comp (ref "U14")
      (value "ADM7170ACPZ-1.3-R7")
      (footprint "SON50P300X300X80-9N")
      (description "6.5 V, 500 mA, Ultralow Noise, High PSRR, Fast Transient Response CMOS LDO")
      (fields (field (name "MF") "Analog Devices"))
      (libsource (lib "ADM7170ACPZ-1.3-R7") (part "ADM7170ACPZ-1.3-R7"))
    )
    (comp (ref "U15")
      (value "TPS51206DSQR")
      (footprint "SON40P200X200X80-11N")
      (fields (field (name "MF") "Texas Instruments"))
      (libsource (lib "TPS51206DSQR") (part "TPS51206DSQR"))
    )
  )
  (nets
    (net (code "2") (name "/1P3_SUPPLY_A") (class "Default")
      (node (ref "C100") (pin "1") (pinfunction "1_1") (pintype "passive"))
      (node (ref "C86") (pin "1") (pinfunction "1_1") (pintype "passive"))
      (node (ref "C87") (pin "1") (pinfunction "1_1") (pintype "passive"))
      (node (ref "C88") (pin "1") (pinfunction "1_1") (pintype "passive"))
      (node (ref "C89") (pin "1") (pinfunction "1_1") (pintype "passive"))
      (node (ref "C90") (pin "1") (pinfunction "1_1") (pintype "passive"))
      (node (ref "C92") (pin "1") (pinfunction "1_1") (pintype "passive"))
      (node (ref "C93") (pin "1") (pinfunction "1_1") (pintype "passive"))
      (node (ref "C95") (pin "1") (pinfunction "1_1") (pintype "passive"))
      (node (ref "C96") (pin "1") (pinfunction "1_1") (pintype "passive"))
      (node (ref "C97") (pin "1") (pinfunction "1_1") (pintype "passive"))
      (node (ref "C98") (pin "1") (pinfunction "1_1") (pintype "passive"))
      (node (ref "C99") (pin "1") (pinfunction "1_1") (pintype "passive"))
      (node (ref "U12") (pin "1") (pinfunction "VOUT_1") (pintype "output"))
      (node (ref "U12") (pin "2") (pinfunction "VOUT_2") (pintype "output"))
      (node (ref "U12") (pin "3") (pinfunction "SENSE_3") (pintype "input"))
    )
    (net (code "3") (name "/1P3_SUPPLY_B") (class "Default")
      (node (ref "C103") (pin "1") (pinfunction "1_1") (pintype "passive"))
      (node (ref "C104") (pin "1") (pinfunction "1_1") (pintype "passive"))
      (node (ref "C105") (pin "1") (pinfunction "1_1") (pintype "passive"))
      (node (ref "C106") (pin "1") (pinfunction "1_1") (pintype "passive"))
      (node (ref "C107") (pin "1") (pinfunction "1_1") (pintype "passive"))
      (node (ref "C109") (pin "1") (pinfunction "1_1") (pintype "passive"))
      (node (ref "C110") (pin "1") (pinfunction "1_1") (pintype "passive"))
      (node (ref "C119") (pin "1") (pinfunction "1_1") (pintype "passive"))
      (node (ref "C120") (pin "1") (pinfunction "1_1") (pintype "passive"))
      (node (ref "C128") (pin "1") (pinfunction "1_1") (pintype "passive"))
      (node (ref "C129") (pin "1") (pinfunction "1_1") (pintype "passive"))
      (node (ref "C131") (pin "1") (pinfunction "1_1") (pintype "passive"))
      (node (ref "C132") (pin "1") (pinfunction "1_1") (pintype "passive"))
      (node (ref "C133") (pin "1") (pinfunction "1_1") (pintype "passive"))
      (node (ref "C134") (pin "1") (pinfunction "1_1") (pintype "passive"))
      (node (ref "U14") (pin "1") (pinfunction "VOUT_1") (pintype "output"))
      (node (ref "U14") (pin "2") (pinfunction "VOUT_2") (pintype "output"))
      (node (ref "U14") (pin "3") (pinfunction "SENSE_3") (pintype "input"))
    )
    (net (code "4") (name "/EN2") (class "Default")
      (node (ref "R65") (pin "2") (pinfunction "2_2") (pintype "passive"))
      (node (ref "R68") (pin "1") (pinfunction "1_1") (pintype "passive"))
      (node (ref "U8") (pin "6") (pinfunction "*EN2_6") (pintype "input"))
    )
    (net (code "5") (name "/EN_DAT_USB") (class "Default")
      (node (ref "R71") (pin "2") (pinfunction "2_2") (pintype "passive"))
      (node (ref "R73") (pin "1") (pinfunction "1_1") (pintype "passive"))
      (node (ref "U11") (pin "6") (pinfunction "*EN2_6") (pintype "input"))
    )
    (net (code "6") (name "/EN_POW_USB") (class "Default")
      (node (ref "R70") (pin "2") (pinfunction "2_2") (pintype "passive"))
      (node (ref "R71") (pin "1") (pinfunction "1_1") (pintype "passive"))
      (node (ref "U11") (pin "3") (pinfunction "EN1_3") (pintype "input"))
    )
    (net (code "7") (name "/EN{slash}UVLO") (class "Default")
      (node (ref "R59") (pin "2") (pinfunction "2_2") (pintype "passive"))
      (node (ref "R60") (pin "1") (pinfunction "1_1") (pintype "passive"))
      (node (ref "U9") (pin "14") (pinfunction "EN/UVLO_14") (pintype "input"))
    )
    (net (code "8") (name "/EXT") (class "Default")
      (node (ref "R63") (pin "2") (pinfunction "2_2") (pintype "passive"))
      (node (ref "R65") (pin "1") (pinfunction "1_1") (pintype "passive"))
      (node (ref "U8") (pin "3") (pinfunction "EN1_3") (pintype "input"))
    )
    (net (code "9") (name "/OVP") (class "Default")
      (node (ref "R60") (pin "2") (pinfunction "2_2") (pintype "passive"))
      (node (ref "R64") (pin "1") (pinfunction "1_1") (pintype "passive"))
      (node (ref "U9") (pin "15") (pinfunction "OVP_15") (pintype "input"))
    )
    (net (code "10") (name "/PG_MPM54304") (class "Default")
      (node (ref "U13") (pin "26") (pinfunction "GPIO_26") (pintype "passive"))
    )
    (net (code "26") (name "/USB_OTG_CPEN") (class "Default")
      (node (ref "U10") (pin "4") (pinfunction "EN_4") (pintype "input"))
    )
    (net (code "27") (name "/USB_VBUS_OTG") (class "Default")
      (node (ref "R62") (pin "1") (pinfunction "1_1") (pintype "passive"))
    )
    (net (code "28") (name "/VCC_MPM") (class "Default")
      (node (ref "C111") (pin "1") (pinfunction "1_1") (pintype "passive"))
      (node (ref "U13") (pin "25") (pinfunction "VCC_25") (pintype "power_in"))
    )
    (net (code "31") (name "1.35V") (class "Default")
      (node (ref "U15") (pin "1") (pinfunction "VDDQSNS_1") (pintype "input"))
    )
    (net (code "32") (name "5V") (class "Default")
      (node (ref "C102") (pin "1") (pinfunction "1_1") (pintype "passive"))
      (node (ref "C77") (pin "1") (pinfunction "1_1") (pintype "passive"))
      (node (ref "F1") (pin "2") (pinfunction "2_2") (pintype "passive"))
      (node (ref "R74") (pin "2") (pinfunction "2_2") (pintype "passive"))
      (node (ref "R75") (pin "2") (pinfunction "2_2") (pintype "passive"))
      (node (ref "U10") (pin "5") (pinfunction "IN_5") (pintype "input"))
      (node (ref "U15") (pin "10") (pinfunction "VDD_10") (pintype "power_in"))
    )
    (net (code "33") (name "GND") (class "Default")
      (node (ref "C100") (pin "2") (pinfunction "2_2") (pintype "passive"))
      (node (ref "C101") (pin "2") (pinfunction "2_2") (pintype "passive"))
      (node (ref "C102") (pin "2") (pinfunction "2_2") (pintype "passive"))
      (node (ref "C103") (pin "2") (pinfunction "2_2") (pintype "passive"))
      (node (ref "C104") (pin "2") (pinfunction "2_2") (pintype "passive"))
      (node (ref "C105") (pin "2") (pinfunction "2_2") (pintype "passive"))
      (node (ref "C106") (pin "2") (pinfunction "2_2") (pintype "passive"))
      (node (ref "C107") (pin "2") (pinfunction "2_2") (pintype "passive"))
      (node (ref "C108") (pin "2") (pinfunction "2_2") (pintype "passive"))
      (node (ref "C109") (pin "2") (pinfunction "2_2") (pintype "passive"))
      (node (ref "C110") (pin "2") (pinfunction "2_2") (pintype "passive"))
      (node (ref "C111") (pin "2") (pinfunction "2_2") (pintype "passive"))
      (node (ref "C112") (pin "2") (pinfunction "2_2") (pintype "passive"))
      (node (ref "C113") (pin "2") (pinfunction "2_2") (pintype "passive"))
      (node (ref "C114") (pin "2") (pinfunction "2_2") (pintype "passive"))
      (node (ref "C115") (pin "2") (pinfunction "2_2") (pintype "passive"))
      (node (ref "C116") (pin "2") (pinfunction "2_2") (pintype "passive"))
      (node (ref "C117") (pin "2") (pinfunction "2_2") (pintype "passive"))
      (node (ref "C118") (pin "2") (pinfunction "2_2") (pintype "passive"))
      (node (ref "C119") (pin "2") (pinfunction "2_2") (pintype "passive"))
      (node (ref "C120") (pin "2") (pinfunction "2_2") (pintype "passive"))
      (node (ref "C121") (pin "2") (pinfunction "2_2") (pintype "passive"))
      (node (ref "C122") (pin "2") (pinfunction "2_2") (pintype "passive"))
      (node (ref "C123") (pin "2") (pinfunction "2_2") (pintype "passive"))
      (node (ref "C124") (pin "2") (pinfunction "2_2") (pintype "passive"))
      (node (ref "C125") (pin "2") (pinfunction "2_2") (pintype "passive"))
      (node (ref "C126") (pin "2") (pinfunction "2_2") (pintype "passive"))
      (node (ref "C127") (pin "2") (pinfunction "2_2") (pintype "passive"))
      (node (ref "C128") (pin "2") (pinfunction "2_2") (pintype "passive"))
      (node (ref "C129") (pin "2") (pinfunction "2_2") (pintype "passive"))
      (node (ref "C130") (pin "2") (pinfunction "2_2") (pintype "passive"))
      (node (ref "C131") (pin "2") (pinfunction "2_2") (pintype "passive"))
      (node (ref "C132") (pin "2") (pinfunction "2_2") (pintype "passive"))
      (node (ref "C133") (pin "2") (pinfunction "2_2") (pintype "passive"))
      (node (ref "C134") (pin "2") (pinfunction "2_2") (pintype "passive"))
      (node (ref "C135") (pin "2") (pinfunction "2_2") (pintype "passive"))
      (node (ref "C136") (pin "2") (pinfunction "2_2") (pintype "passive"))
      (node (ref "C137") (pin "2") (pinfunction "2_2") (pintype "passive"))
      (node (ref "C138") (pin "2") (pinfunction "2_2") (pintype "passive"))
      (node (ref "C139") (pin "2") (pinfunction "2_2") (pintype "passive"))
      (node (ref "C140") (pin "2") (pinfunction "2_2") (pintype "passive"))
      (node (ref "C141") (pin "2") (pinfunction "2_2") (pintype "passive"))
      (node (ref "C142") (pin "2") (pinfunction "2_2") (pintype "passive"))
      (node (ref "C64") (pin "2") (pinfunction "2_2") (pintype "passive"))
      (node (ref "C65") (pin "2") (pinfunction "2_2") (pintype "passive"))
      (node (ref "C66") (pin "2") (pinfunction "2_2") (pintype "passive"))
      (node (ref "C68") (pin "2") (pinfunction "2_2") (pintype "passive"))
      (node (ref "C69") (pin "2") (pinfunction "2_2") (pintype "passive"))
      (node (ref "C70") (pin "2") (pinfunction "2_2") (pintype "passive"))
      (node (ref "C71") (pin "2") (pinfunction "2_2") (pintype "passive"))
      (node (ref "C72") (pin "2") (pinfunction "2_2") (pintype "passive"))
      (node (ref "C73") (pin "1") (pinfunction "1_1") (pintype "passive"))
      (node (ref "C74") (pin "2") (pinfunction "2_2") (pintype "passive"))
      (node (ref "C75") (pin "2") (pinfunction "2_2") (pintype "passive"))
      (node (ref "C76") (pin "2") (pinfunction "2_2") (pintype "passive"))
      (node (ref "C77") (pin "2") (pinfunction "2_2") (pintype "passive"))
      (node (ref "C78") (pin "2") (pinfunction "2_2") (pintype "passive"))
      (node (ref "C79") (pin "2") (pinfunction "2_2") (pintype "passive"))
      (node (ref "C80") (pin "2") (pinfunction "2_2") (pintype "passive"))
      (node (ref "C81") (pin "2") (pinfunction "2_2") (pintype "passive"))
      (node (ref "C82") (pin "2") (pinfunction "2_2") (pintype "passive"))
      (node (ref "C83") (pin "2") (pinfunction "2_2") (pintype "passive"))
      (node (ref "C84") (pin "2") (pinfunction "2_2") (pintype "passive"))
      (node (ref "C85") (pin "2") (pinfunction "2_2") (pintype "passive"))
      (node (ref "C86") (pin "2") (pinfunction "2_2") (pintype "passive"))
      (node (ref "C87") (pin "2") (pinfunction "2_2") (pintype "passive"))
      (node (ref "C88") (pin "2") (pinfunction "2_2") (pintype "passive"))
      (node (ref "C89") (pin "2") (pinfunction "2_2") (pintype "passive"))
      (node (ref "C90") (pin "2") (pinfunction "2_2") (pintype "passive"))
      (node (ref "C91") (pin "2") (pinfunction "2_2") (pintype "passive"))
      (node (ref "C92") (pin "2") (pinfunction "2_2") (pintype "passive"))
      (node (ref "C93") (pin "2") (pinfunction "2_2") (pintype "passive"))
      (node (ref "C94") (pin "2") (pinfunction "2_2") (pintype "passive"))
      (node (ref "C95") (pin "2") (pinfunction "2_2") (pintype "passive"))
      (node (ref "C96") (pin "2") (pinfunction "2_2") (pintype "passive"))
      (node (ref "C97") (pin "2") (pinfunction "2_2") (pintype "passive"))
      (node (ref "C98") (pin "2") (pinfunction "2_2") (pintype "passive"))
      (node (ref "C99") (pin "2") (pinfunction "2_2") (pintype "passive"))
      (node (ref "J6") (pin "2") (pinfunction "2_2") (pintype "passive"))
      (node (ref "J6") (pin "3") (pinfunction "3_3") (pintype "passive"))
      (node (ref "R57") (pin "1") (pinfunction "1_1") (pintype "passive"))
      (node (ref "R61") (pin "2") (pinfunction "2_2") (pintype "passive"))
      (node (ref "R64") (pin "2") (pinfunction "2_2") (pintype "passive"))
      (node (ref "R66") (pin "2") (pinfunction "2_2") (pintype "passive"))
      (node (ref "R67") (pin "2") (pinfunction "2_2") (pintype "passive"))
      (node (ref "R68") (pin "2") (pinfunction "2_2") (pintype "passive"))
      (node (ref "R69") (pin "2") (pinfunction "2_2") (pintype "passive"))
      (node (ref "R72") (pin "2") (pinfunction "2_2") (pintype "passive"))
      (node (ref "R73") (pin "2") (pinfunction "2_2") (pintype "passive"))
      (node (ref "R77") (pin "2") (pinfunction "2_2") (pintype "passive"))
      (node (ref "U10") (pin "2") (pinfunction "GND_2") (pintype "power_in"))
      (node (ref "U11") (pin "17") (pinfunction "GND_17") (pintype "power_in"))
      (node (ref "U12") (pin "6") (pinfunction "GND_6") (pintype "power_in"))
      (node (ref "U12") (pin "9") (pinfunction "EXP_9") (pintype "power_in"))
      (node (ref "U13") (pin "10") (pinfunction "GND_10") (pintype "power_in"))
      (node (ref "U13") (pin "13") (pinfunction "GND_13") (pintype "power_in"))
      (node (ref "U13") (pin "16") (pinfunction "GND_16") (pintype "power_in"))
      (node (ref "U13") (pin "17") (pinfunction "SGND1_17") (pintype "power_in"))
      (node (ref "U13") (pin "2") (pinfunction "GND_2") (pintype "power_in"))
      (node (ref "U13") (pin "20") (pinfunction "GND_20") (pintype "power_in"))
      (node (ref "U13") (pin "21") (pinfunction "GND_21") (pintype "power_in"))
      (node (ref "U13") (pin "27") (pinfunction "GND_27") (pintype "power_in"))
      (node (ref "U13") (pin "30") (pinfunction "SGND2_30") (pintype "power_in"))
      (node (ref "U13") (pin "33") (pinfunction "GND_33") (pintype "power_in"))
      (node (ref "U13") (pin "5") (pinfunction "GND_5") (pintype "power_in"))
      (node (ref "U13") (pin "7") (pinfunction "GND_7") (pintype "power_in"))
      (node (ref "U14") (pin "6") (pinfunction "GND_6") (pintype "power_in"))
      (node (ref "U14") (pin "9") (pinfunction "EXP_9") (pintype "power_in"))
      (node (ref "U15") (pin "11") (pinfunction "EXP_11") (pintype "passive"))
      (node (ref "U15") (pin "4") (pinfunction "PGND_4") (pintype "power_in"))
      (node (ref "U15") (pin "8") (pinfunction "GND_8") (pintype "power_in"))
      (node (ref "U7") (pin "1") (pinfunction "PGND_1") (pintype "power_in"))
      (node (ref "U7") (pin "9") (pinfunction "AGND_9") (pintype "power_in"))
      (node (ref "U8") (pin "17") (pinfunction "GND_17") (pintype "power_in"))
      (node (ref "U9") (pin "16") (pinfunction "GND_16") (pintype "power_in"))
      (node (ref "U9") (pin "21") (pinfunction "EPAD_21") (pintype "power_in"))
    )
    (net (code "34") (name "Net-(C68-Pad1)") (class "Default")
      (node (ref "C68") (pin "1") (pinfunction "1_1") (pintype "passive"))
      (node (ref "R58") (pin "1") (pinfunction "1_1") (pintype "passive"))
    )
    (net (code "35") (name "Net-(C137-Pad1)") (class "Default")
      (node (ref "C137") (pin "1") (pinfunction "1_1") (pintype "passive"))
      (node (ref "C138") (pin "1") (pinfunction "1_1") (pintype "passive"))
      (node (ref "C139") (pin "1") (pinfunction "1_1") (pintype "passive"))
      (node (ref "C140") (pin "1") (pinfunction "1_1") (pintype "passive"))
      (node (ref "C141") (pin "1") (pinfunction "1_1") (pintype "passive"))
      (node (ref "C142") (pin "1") (pinfunction "1_1") (pintype "passive"))
      (node (ref "FB12") (pin "1") (pintype "passive"))
    )
    (net (code "36") (name "Net-(F1-Pad1)") (class "Default")
      (node (ref "F1") (pin "1") (pinfunction "1_1") (pintype "passive"))
      (node (ref "U8") (pin "10") (pinfunction "OUT2_10") (pintype "output"))
      (node (ref "U8") (pin "15") (pinfunction "OUT1_15") (pintype "output"))
      (node (ref "U8") (pin "16") (pinfunction "OUT1_16") (pintype "output"))
      (node (ref "U8") (pin "9") (pinfunction "OUT2_9") (pintype "output"))
    )
    (net (code "37") (name "Net-(U7-BOOT)") (class "Default")
      (node (ref "C67") (pin "1") (pinfunction "1_1") (pintype "passive"))
      (node (ref "U7") (pin "7") (pinfunction "BOOT_7") (pintype "bidirectional"))
    )
    (net (code "38") (name "Net-(U7-FB)") (class "Default")
      (node (ref "R57") (pin "2") (pinfunction "2_2") (pintype "passive"))
      (node (ref "R58") (pin "2") (pinfunction "2_2") (pintype "passive"))
      (node (ref "U7") (pin "5") (pinfunction "FB_5") (pintype "input"))
    )
    (net (code "39") (name "Net-(U7-SW)") (class "Default")
      (node (ref "C67") (pin "2") (pinfunction "2_2") (pintype "passive"))
      (node (ref "L5") (pin "2") (pinfunction "2_2") (pintype "passive"))
      (node (ref "U7") (pin "8") (pinfunction "SW_8") (pintype "bidirectional"))
    )
    (net (code "40") (name "Net-(U7-VCC)") (class "Default")
      (node (ref "C66") (pin "1") (pinfunction "1_1") (pintype "passive"))
      (node (ref "U7") (pin "6") (pinfunction "VCC_6") (pintype "power_in"))
    )
    (net (code "41") (name "Net-(U8-CLIM1)") (class "Default")
      (node (ref "R61") (pin "1") (pinfunction "1_1") (pintype "passive"))
      (node (ref "U8") (pin "4") (pinfunction "CLIM1_4") (pintype "passive"))
    )
    (net (code "42") (name "Net-(U8-CLIM2)") (class "Default")
      (node (ref "R67") (pin "1") (pinfunction "1_1") (pintype "passive"))
      (node (ref "U8") (pin "5") (pinfunction "CLIM2_5") (pintype "passive"))
    )
    (net (code "43") (name "Net-(U9-DVDT)") (class "Default")
      (node (ref "C73") (pin "2") (pinfunction "2_2") (pintype "passive"))
      (node (ref "U9") (pin "18") (pinfunction "DVDT_18") (pintype "bidirectional"))
    )
    (net (code "44") (name "Net-(U9-ILIM)") (class "Default")
      (node (ref "R66") (pin "1") (pinfunction "1_1") (pintype "passive"))
      (node (ref "U9") (pin "17") (pinfunction "ILIM_17") (pintype "bidirectional"))
    )
    (net (code "45") (name "Net-(U11-CLIM1)") (class "Default")
      (node (ref "R69") (pin "1") (pinfunction "1_1") (pintype "passive"))
      (node (ref "U11") (pin "4") (pinfunction "CLIM1_4") (pintype "passive"))
    )
    (net (code "46") (name "Net-(U11-CLIM2)") (class "Default")
      (node (ref "R72") (pin "1") (pinfunction "1_1") (pintype "passive"))
      (node (ref "U11") (pin "5") (pinfunction "CLIM2_5") (pintype "passive"))
    )
    (net (code "47") (name "Net-(U12-SS)") (class "Default")
      (node (ref "C94") (pin "1") (pinfunction "1_1") (pintype "passive"))
      (node (ref "U12") (pin "4") (pinfunction "SS_4") (pintype "passive"))
    )
    (net (code "48") (name "Net-(U13-EN)") (class "Default")
      (node (ref "C130") (pin "1") (pinfunction "1_1") (pintype "passive"))
      (node (ref "R76") (pin "2") (pinfunction "2_2") (pintype "passive"))
      (node (ref "R77") (pin "1") (pinfunction "1_1") (pintype "passive"))
      (node (ref "U13") (pin "19") (pinfunction "EN_19") (pintype "passive"))
    )
    (net (code "49") (name "Net-(U14-SS)") (class "Default")
      (node (ref "C118") (pin "1") (pinfunction "1_1") (pintype "passive"))
      (node (ref "U14") (pin "4") (pinfunction "SS_4") (pintype "passive"))
    )
    (net (code "50") (name "Net-(U15-S3)") (class "Default")
      (node (ref "R75") (pin "1") (pinfunction "1_1") (pintype "passive"))
      (node (ref "U15") (pin "7") (pinfunction "S3_7") (pintype "input"))
    )
    (net (code "51") (name "Net-(U15-S5)") (class "Default")
      (node (ref "R74") (pin "1") (pinfunction "1_1") (pintype "passive"))
      (node (ref "U15") (pin "9") (pinfunction "S5_9") (pintype "input"))
    )
    (net (code "52") (name "OUTA") (class "Default")
      (node (ref "C82") (pin "1") (pinfunction "1_1") (pintype "passive"))
      (node (ref "C83") (pin "1") (pinfunction "1_1") (pintype "passive"))
      (node (ref "C84") (pin "1") (pinfunction "1_1") (pintype "passive"))
      (node (ref "U11") (pin "10") (pinfunction "OUT2_10") (pintype "output"))
      (node (ref "U11") (pin "15") (pinfunction "OUT1_15") (pintype "output"))
      (node (ref "U11") (pin "16") (pinfunction "OUT1_16") (pintype "output"))
      (node (ref "U11") (pin "9") (pinfunction "OUT2_9") (pintype "output"))
      (node (ref "U8") (pin "7") (pinfunction "IN2_7") (pintype "power_in"))
      (node (ref "U8") (pin "8") (pinfunction "IN2_8") (pintype "power_in"))
    )
    (net (code "53") (name "USB_VBUS") (class "Default")
      (node (ref "C74") (pin "1") (pinfunction "1_1") (pintype "passive"))
      (node (ref "C75") (pin "1") (pinfunction "1_1") (pintype "passive"))
      (node (ref "C76") (pin "1") (pinfunction "1_1") (pintype "passive"))
      (node (ref "C85") (pin "1") (pinfunction "1_1") (pintype "passive"))
      (node (ref "FB11") (pin "1") (pintype "passive"))
      (node (ref "R59") (pin "1") (pinfunction "1_1") (pintype "passive"))
      (node (ref "R62") (pin "2") (pinfunction "2_2") (pintype "passive"))
      (node (ref "U10") (pin "1") (pinfunction "OUT_1") (pintype "output"))
      (node (ref "U11") (pin "7") (pinfunction "IN2_7") (pintype "power_in"))
      (node (ref "U11") (pin "8") (pinfunction "IN2_8") (pintype "power_in"))
      (node (ref "U9") (pin "10") (pinfunction "IN_10") (pintype "input"))
      (node (ref "U9") (pin "11") (pinfunction "IN_11") (pintype "input"))
      (node (ref "U9") (pin "12") (pinfunction "IN_12") (pintype "input"))
      (node (ref "U9") (pin "13") (pinfunction "IN_13") (pintype "input"))
      (node (ref "U9") (pin "9") (pinfunction "IN_9") (pintype "input"))
    )
    (net (code "54") (name "VDD_1.0V") (class "Default")
      (node (ref "C122") (pin "1") (pinfunction "1_1") (pintype "passive"))
      (node (ref "C123") (pin "1") (pinfunction "1_1") (pintype "passive"))
      (node (ref "U13") (pin "14") (pinfunction "VOUT1_14") (pintype "output"))
      (node (ref "U13") (pin "15") (pinfunction "VOUT1_15") (pintype "output"))
      (node (ref "U13") (pin "18") (pinfunction "FB1_18") (pintype "bidirectional"))
    )
    (net (code "55") (name "VDD_1.5V") (class "Default")
      (node (ref "C121") (pin "1") (pinfunction "1_1") (pintype "passive"))
      (node (ref "U13") (pin "22") (pinfunction "VOUT4_22") (pintype "output"))
      (node (ref "U13") (pin "23") (pinfunction "VOUT4_23") (pintype "output"))
      (node (ref "U13") (pin "24") (pinfunction "FB4_24") (pintype "bidirectional"))
    )
    (net (code "56") (name "VDD_1.8V") (class "Default")
      (node (ref "C101") (pin "1") (pinfunction "1_1") (pintype "passive"))
      (node (ref "C124") (pin "1") (pinfunction "1_1") (pintype "passive"))
      (node (ref "C125") (pin "1") (pinfunction "1_1") (pintype "passive"))
      (node (ref "C135") (pin "1") (pinfunction "1_1") (pintype "passive"))
      (node (ref "C136") (pin "1") (pinfunction "1_1") (pintype "passive"))
      (node (ref "FB12") (pin "2") (pintype "passive"))
      (node (ref "U13") (pin "1") (pinfunction "VOUT3_1") (pintype "output"))
      (node (ref "U13") (pin "31") (pinfunction "FB3_31") (pintype "bidirectional"))
      (node (ref "U13") (pin "32") (pinfunction "VOUT3_32") (pintype "output"))
      (node (ref "U15") (pin "2") (pinfunction "VLDOIN_2") (pintype "input"))
    )
    (net (code "57") (name "VDD_3.3V") (class "Default")
      (node (ref "C108") (pin "1") (pinfunction "1_1") (pintype "passive"))
      (node (ref "C114") (pin "1") (pinfunction "1_1") (pintype "passive"))
      (node (ref "C115") (pin "1") (pinfunction "1_1") (pintype "passive"))
      (node (ref "C91") (pin "1") (pinfunction "1_1") (pintype "passive"))
      (node (ref "U12") (pin "5") (pinfunction "EN_5") (pintype "input"))
      (node (ref "U12") (pin "7") (pinfunction "VIN_7") (pintype "input"))
      (node (ref "U12") (pin "8") (pinfunction "VIN_8") (pintype "input"))
      (node (ref "U13") (pin "6") (pinfunction "FB2_6") (pintype "bidirectional"))
      (node (ref "U13") (pin "8") (pinfunction "VOUT2_8") (pintype "output"))
      (node (ref "U13") (pin "9") (pinfunction "VOUT2_9") (pintype "output"))
      (node (ref "U14") (pin "5") (pinfunction "EN_5") (pintype "input"))
      (node (ref "U14") (pin "7") (pinfunction "VIN_7") (pintype "input"))
      (node (ref "U14") (pin "8") (pinfunction "VIN_8") (pintype "input"))
    )
    (net (code "58") (name "VDD_12V") (class "Default")
      (node (ref "J6") (pin "1") (pinfunction "1_1") (pintype "passive"))
      (node (ref "L6") (pin "1") (pinfunction "1_1") (pintype "passive"))
    )
    (net (code "59") (name "VDD_12V_FILTERED") (class "Default")
      (node (ref "C112") (pin "1") (pinfunction "1_1") (pintype "passive"))
      (node (ref "C113") (pin "1") (pinfunction "1_1") (pintype "passive"))
      (node (ref "C64") (pin "1") (pinfunction "1_1") (pintype "passive"))
      (node (ref "C65") (pin "1") (pinfunction "1_1") (pintype "passive"))
      (node (ref "C80") (pin "1") (pinfunction "1_1") (pintype "passive"))
      (node (ref "C81") (pin "1") (pinfunction "1_1") (pintype "passive"))
      (node (ref "L6") (pin "2") (pinfunction "2_2") (pintype "passive"))
      (node (ref "R76") (pin "1") (pinfunction "1_1") (pintype "passive"))
      (node (ref "U13") (pin "28") (pinfunction "VIN_28") (pintype "passive"))
      (node (ref "U13") (pin "29") (pinfunction "VIN_29") (pintype "passive"))
      (node (ref "U7") (pin "2") (pinfunction "VIN_2") (pintype "input"))
      (node (ref "U7") (pin "3") (pinfunction "EN_3") (pintype "input"))
      (node (ref "U9") (pin "3") (pinfunction "PGTH_3") (pintype "input"))
      (node (ref "U9") (pin "4") (pinfunction "OUT_4") (pintype "output"))
      (node (ref "U9") (pin "5") (pinfunction "OUT_5") (pintype "output"))
      (node (ref "U9") (pin "6") (pinfunction "OUT_6") (pintype "output"))
      (node (ref "U9") (pin "7") (pinfunction "OUT_7") (pintype "output"))
      (node (ref "U9") (pin "8") (pinfunction "OUT_8") (pintype "output"))
    )
    (net (code "60") (name "VIN_5V_EXT_PLUG") (class "Default")
      (node (ref "C69") (pin "1") (pinfunction "1_1") (pintype "passive"))
      (node (ref "C70") (pin "1") (pinfunction "1_1") (pintype "passive"))
      (node (ref "C71") (pin "1") (pinfunction "1_1") (pintype "passive"))
      (node (ref "C72") (pin "1") (pinfunction "1_1") (pintype "passive"))
      (node (ref "L5") (pin "1") (pinfunction "1_1") (pintype "passive"))
      (node (ref "R63") (pin "1") (pinfunction "1_1") (pintype "passive"))
      (node (ref "U8") (pin "1") (pinfunction "IN1_1") (pintype "power_in"))
      (node (ref "U8") (pin "2") (pinfunction "IN1_2") (pintype "power_in"))
    )
    (net (code "61") (name "VIN_5V_USB_DATA") (class "Default")
      (node (ref "C78") (pin "1") (pinfunction "1_1") (pintype "passive"))
      (node (ref "FB11") (pin "2") (pintype "passive"))
    )
    (net (code "62") (name "VIN_5V_USB_POWER") (class "Default")
      (node (ref "C79") (pin "1") (pinfunction "1_1") (pintype "passive"))
      (node (ref "R70") (pin "1") (pinfunction "1_1") (pintype "passive"))
      (node (ref "U11") (pin "1") (pinfunction "IN1_1") (pintype "power_in"))
      (node (ref "U11") (pin "2") (pinfunction "IN1_2") (pintype "power_in"))
    )
    (net (code "63") (name "VTTVREF") (class "Default")
      (node (ref "C126") (pin "1") (pinfunction "1_1") (pintype "passive"))
      (node (ref "C127") (pin "1") (pinfunction "1_1") (pintype "passive"))
      (node (ref "U15") (pin "6") (pinfunction "VTTREF_6") (pintype "output"))
    )
    (net (code "64") (name "VTT_0P75") (class "Default")
      (node (ref "C116") (pin "1") (pinfunction "1_1") (pintype "passive"))
      (node (ref "C117") (pin "1") (pinfunction "1_1") (pintype "passive"))
      (node (ref "U15") (pin "3") (pinfunction "VTT_3") (pintype "output"))
      (node (ref "U15") (pin "5") (pinfunction "VTTSNS_5") (pintype "input"))
    )
    (net (code "65") (name "unconnected-(U7-PG-Pad4)") (class "Default")
      (node (ref "U7") (pin "4") (pinfunction "PG_4") (pintype "output"))
    )
    (net (code "66") (name "unconnected-(U8-*STAT1-Pad14)") (class "Default")
      (node (ref "U8") (pin "14") (pinfunction "*STAT1_14") (pintype "output"))
    )
    (net (code "67") (name "unconnected-(U8-*STAT2-Pad11)") (class "Default")
      (node (ref "U8") (pin "11") (pinfunction "*STAT2_11") (pintype "output"))
    )
    (net (code "68") (name "unconnected-(U8-*WARN1-Pad13)") (class "Default")
      (node (ref "U8") (pin "13") (pinfunction "*WARN1_13") (pintype "output"))
    )
    (net (code "69") (name "unconnected-(U8-*WARN2-Pad12)") (class "Default")
      (node (ref "U8") (pin "12") (pinfunction "*WARN2_12") (pintype "output"))
    )
    (net (code "70") (name "unconnected-(U9-*FLT-Pad20)") (class "Default")
      (node (ref "U9") (pin "20") (pinfunction "*FLT_20") (pintype "output+no_connect"))
    )
    (net (code "71") (name "unconnected-(U9-DEVSLP-Pad1)") (class "Default")
      (node (ref "U9") (pin "1") (pinfunction "DEVSLP_1") (pintype "input+no_connect"))
    )
    (net (code "72") (name "unconnected-(U9-IMON-Pad19)") (class "Default")
      (node (ref "U9") (pin "19") (pinfunction "IMON_19") (pintype "output+no_connect"))
    )
    (net (code "73") (name "unconnected-(U9-PGOOD-Pad2)") (class "Default")
      (node (ref "U9") (pin "2") (pinfunction "PGOOD_2") (pintype "output+no_connect"))
    )
    (net (code "74") (name "unconnected-(U10-FLG-Pad3)") (class "Default")
      (node (ref "U10") (pin "3") (pinfunction "FLG_3") (pintype "passive"))
    )
    (net (code "75") (name "unconnected-(U11-*STAT1-Pad14)") (class "Default")
      (node (ref "U11") (pin "14") (pinfunction "*STAT1_14") (pintype "output"))
    )
    (net (code "76") (name "unconnected-(U11-*STAT2-Pad11)") (class "Default")
      (node (ref "U11") (pin "11") (pinfunction "*STAT2_11") (pintype "output"))
    )
    (net (code "77") (name "unconnected-(U11-*WARN1-Pad13)") (class "Default")
      (node (ref "U11") (pin "13") (pinfunction "*WARN1_13") (pintype "output"))
    )
    (net (code "78") (name "unconnected-(U11-*WARN2-Pad12)") (class "Default")
      (node (ref "U11") (pin "12") (pinfunction "*WARN2_12") (pintype "output"))
    )
    (net (code "79") (name "unconnected-(U13-SCL-Pad4)") (class "Default")
      (node (ref "U13") (pin "4") (pinfunction "SCL_4") (pintype "passive+no_connect"))
    )
    (net (code "80") (name "unconnected-(U13-SDA-Pad3)") (class "Default")
      (node (ref "U13") (pin "3") (pinfunction "SDA_3") (pintype "passive+no_connect"))
    )
    (net (code "81") (name "unconnected-(U13-SW1-Pad12)") (class "Default")
      (node (ref "U13") (pin "12") (pinfunction "SW1_12") (pintype "bidirectional+no_connect"))
    )
    (net (code "82") (name "unconnected-(U13-SW2-Pad11)") (class "Default")
      (node (ref "U13") (pin "11") (pinfunction "SW2_11") (pintype "bidirectional+no_connect"))
    )
  )
)
